# LCD.net
KiCad netlist of a schematic drawn in Altium Designer
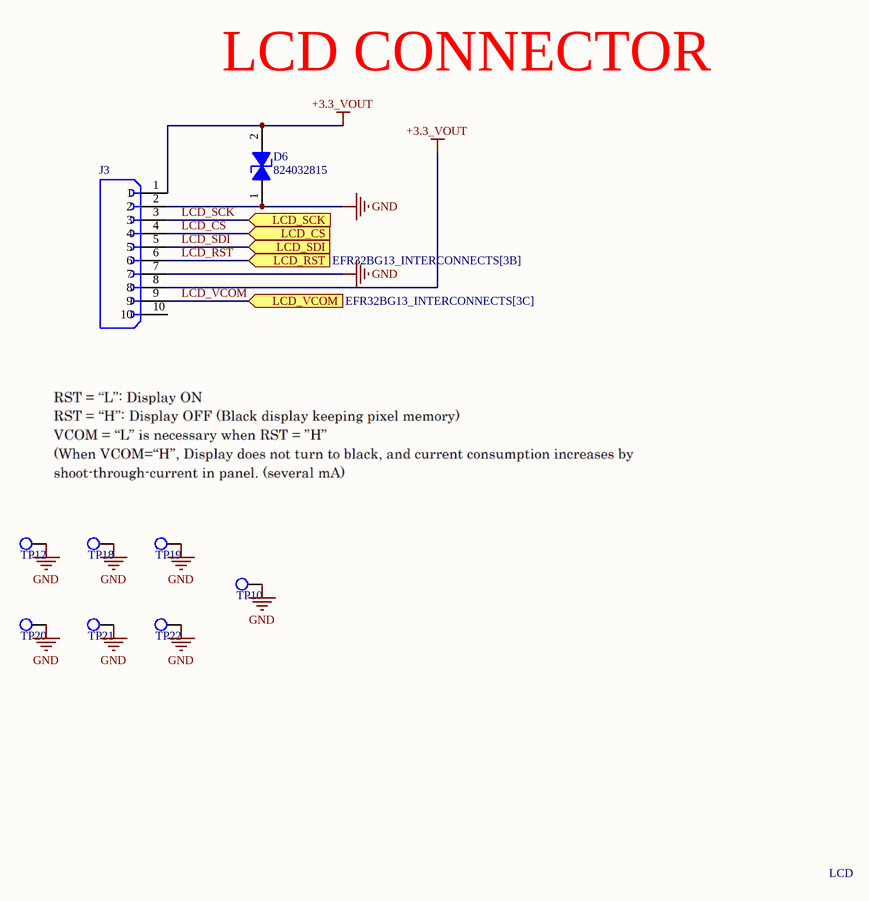
[diagram p0: LCD.SchDoc]

(export (version "E")
  (design (tool "Eeschema 10.0.6"))
  (components
    (comp (ref "D6")
      (value "824032815")
      (footprint "WE-TVS_DFN1610-2L")
      (description "824032815 Tvs Diode, Bidir, 5V, Dfn1610 Rohs Compliant: Yes ¦Wurth Elektronik 824032815")
      (libsource (lib "LPEDT_Components") (part "TVS Diode ESD Protection"))
    )
    (comp (ref "J3")
      (value "~")
      (footprint "HRS_TF13BA-10S-0.4SH(800)")
      (fields (field (name "MP") "TF13BA-10S-0.4SH(800)"))
      (libsource (lib "LPEDT_Components") (part "TF13BA-10S-0.4SH(800)"))
    )
    (comp (ref "TP10")
      (value "~")
      (footprint "Test Point")
      (libsource (lib "LPEDT_Components") (part "Test Point"))
    )
    (comp (ref "TP12")
      (value "~")
      (footprint "Test Point")
      (libsource (lib "LPEDT_Components") (part "Test Point"))
    )
    (comp (ref "TP18")
      (value "~")
      (footprint "Test Point")
      (libsource (lib "LPEDT_Components") (part "Test Point"))
    )
    (comp (ref "TP19")
      (value "~")
      (footprint "Test Point")
      (libsource (lib "LPEDT_Components") (part "Test Point"))
    )
    (comp (ref "TP20")
      (value "~")
      (footprint "Test Point")
      (libsource (lib "LPEDT_Components") (part "Test Point"))
    )
    (comp (ref "TP21")
      (value "~")
      (footprint "Test Point")
      (libsource (lib "LPEDT_Components") (part "Test Point"))
    )
    (comp (ref "TP22")
      (value "~")
      (footprint "Test Point")
      (libsource (lib "LPEDT_Components") (part "Test Point"))
    )
  )
  (nets
    (net (code "1") (name "+3.3_VOUT") (class "Default")
      (node (ref "D6") (pin "2") (pinfunction "GND_2") (pintype "passive"))
      (node (ref "J3") (pin "1") (pinfunction "1_1") (pintype "passive"))
      (node (ref "J3") (pin "8") (pinfunction "8_8") (pintype "passive"))
    )
    (net (code "2") (name "/LCD_CS") (class "Default")
      (node (ref "J3") (pin "4") (pinfunction "4_4") (pintype "passive"))
    )
    (net (code "3") (name "/LCD_RST") (class "Default")
      (node (ref "J3") (pin "6") (pinfunction "6_6") (pintype "passive"))
    )
    (net (code "4") (name "/LCD_SCK") (class "Default")
      (node (ref "J3") (pin "3") (pinfunction "3_3") (pintype "passive"))
    )
    (net (code "5") (name "/LCD_SDI") (class "Default")
      (node (ref "J3") (pin "5") (pinfunction "5_5") (pintype "passive"))
    )
    (net (code "6") (name "/LCD_VCOM") (class "Default")
      (node (ref "J3") (pin "9") (pinfunction "9_9") (pintype "passive"))
    )
    (net (code "7") (name "GND") (class "Default")
      (node (ref "D6") (pin "1") (pinfunction "I/O_1_1") (pintype "passive"))
      (node (ref "J3") (pin "2") (pinfunction "2_2") (pintype "passive"))
      (node (ref "J3") (pin "7") (pinfunction "7_7") (pintype "passive"))
      (node (ref "TP10") (pin "1") (pinfunction "1_1") (pintype "passive"))
      (node (ref "TP12") (pin "1") (pinfunction "1_1") (pintype "passive"))
      (node (ref "TP18") (pin "1") (pinfunction "1_1") (pintype "passive"))
      (node (ref "TP19") (pin "1") (pinfunction "1_1") (pintype "passive"))
      (node (ref "TP20") (pin "1") (pinfunction "1_1") (pintype "passive"))
      (node (ref "TP21") (pin "1") (pinfunction "1_1") (pintype "passive"))
      (node (ref "TP22") (pin "1") (pinfunction "1_1") (pintype "passive"))
    )
    (net (code "8") (name "unconnected-(J3-Pad10)") (class "Default")
      (node (ref "J3") (pin "10") (pinfunction "10_10") (pintype "passive"))
    )
  )
)
